# Control_circuit.net
KiCad netlist of a schematic drawn in Altium Designer
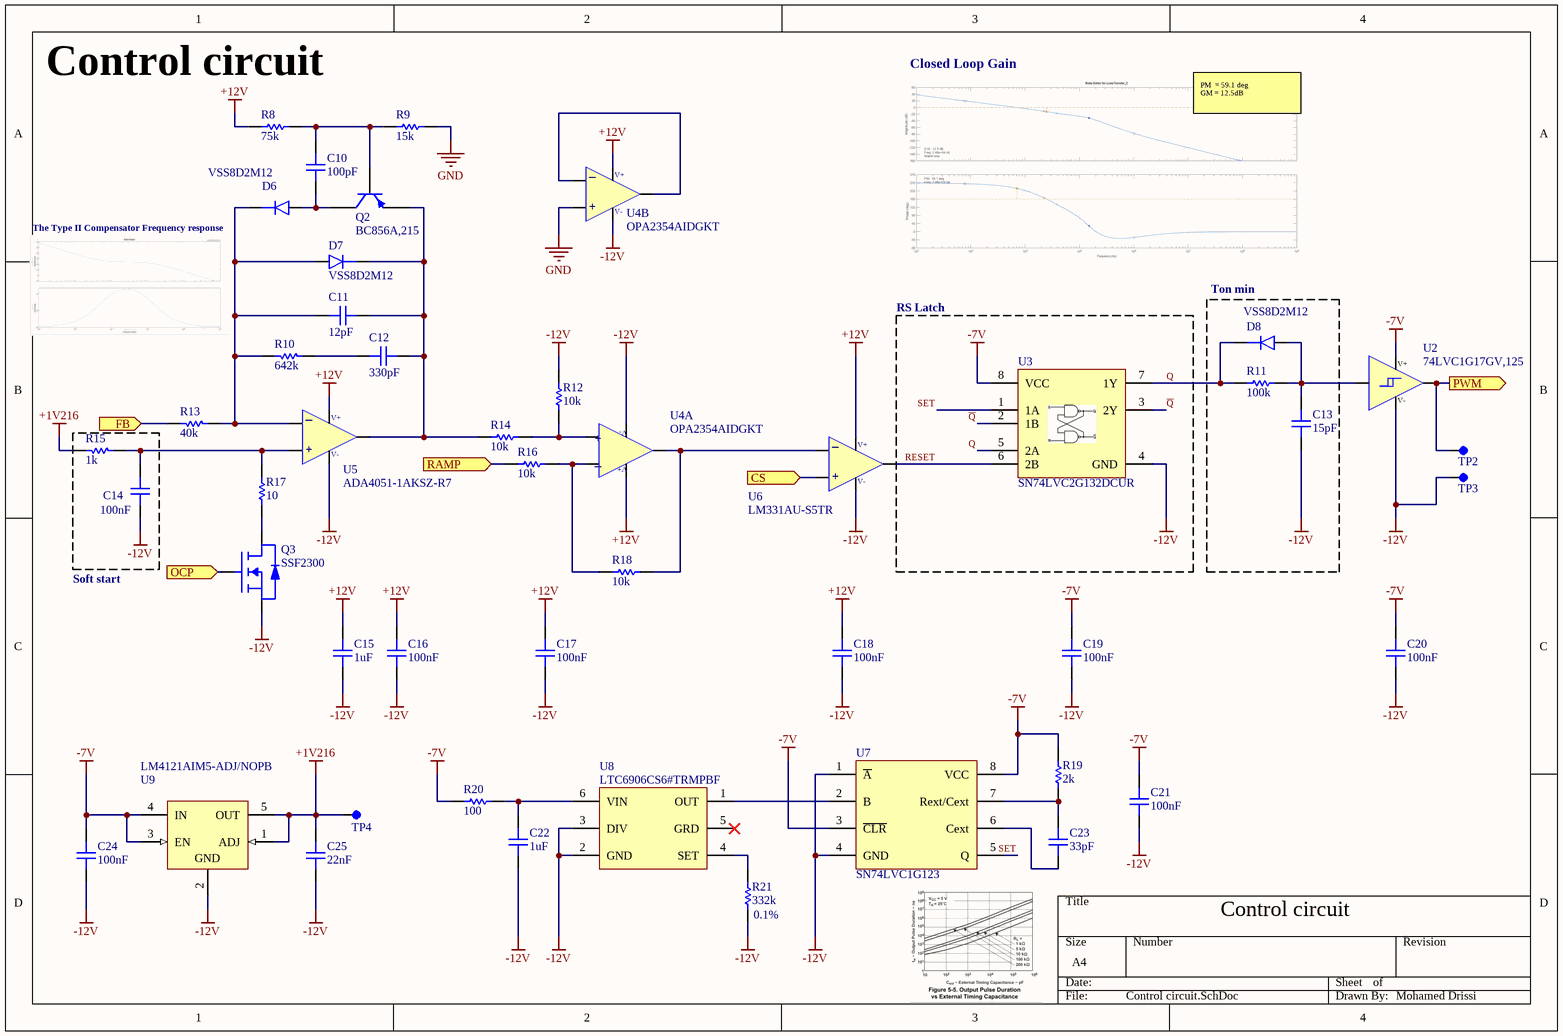
[diagram p0: Control circuit.SchDoc]

(export (version "E")
  (design (tool "Eeschema 10.0.6"))
  (components
    (comp (ref "C10")
      (value "GCM1885C2A101JA16D")
      (footprint "Cap_0603")
      (description "100V 100pF C0G ±5% 0603 Multilayer Ceramic Capacitors MLCC - SMD/SMT ROHS")
      (fields
        (field (name "MANUFACTURER") "Murata")
        (field (name "TOLERANCE") "5%")
        (field (name "CAPACITANCE") "100pF")
      )
      (libsource (lib "Inverting buck boost") (part "Murata GCM1885C2A101JA16D"))
    )
    (comp (ref "C11")
      (value "VJ0603A120KXJCW1BC")
      (footprint "cap_0603")
      (fields
        (field (name "MANUFACTURER") "Vishay")
        (field (name "TOLERANCE") "10%")
        (field (name "CAPACITANCE") "12pF")
      )
      (libsource (lib "Inverting buck boost") (part "Vishay VJ0603A120KXJCW1BC"))
    )
    (comp (ref "C12")
      (value "885012006026")
      (footprint "Cap_0603")
      (description "WCAP-CSGP 0603 (1608Metric) Ceramic Capacitor 0.063Lx0.031W 1.60mmx0.80mm C0G NP0 ±5% 330pF")
      (fields
        (field (name "MANUFACTURER") "Wurth Elektronik")
        (field (name "TOLERANCE") "5%")
        (field (name "CAPACITANCE") "330pF")
      )
      (libsource (lib "Inverting buck boost") (part "Wurth 885012006026"))
    )
    (comp (ref "C13")
      (value "CL10C150JC81PNC")
      (footprint "cap_0603")
      (description "100V 15pF C0G 卤5% 0603 Multilayer Ceramic Capacitors MLCC - SMD/SMT ROHS")
      (fields
        (field (name "MANUFACTURER") "Samsung Electro-Mechanics")
        (field (name "TOLERANCE") "5%")
        (field (name "CAPACITANCE") "15pF")
      )
      (libsource (lib "Inverting buck boost") (part "Samsung CL10C150JC81PNC"))
    )
    (comp (ref "C14")
      (value "GMC10X7R104K100NT")
      (footprint "cap_0603")
      (description "100V 100nF X7R ±10% 0603 Multilayer Ceramic Capacitors MLCC - SMD/SMT ROHS")
      (fields (field (name "MANUFACTURER") "Cal-Chip Electronics") (field (name "CAPACITANCE") "100nF"))
      (libsource (lib "Inverting buck boost") (part "Cal-chip GMC10X7R104K100NT"))
    )
    (comp (ref "C15")
      (value "885382208005")
      (footprint "cap_1206")
      (description "WCAP-CSST 1206 (3216Metric) ceramic capacitor 0.126Lx0.063W 3.20mmx1.60mm X7R ±10% 1muF")
      (fields (field (name "MANUFACTURER") "Wurth Elektronik") (field (name "CAPACITANCE") "1uF"))
      (libsource (lib "Inverting buck boost") (part "Wurth 885382208005"))
    )
    (comp (ref "C16")
      (value "GMC10X7R104K100NT")
      (footprint "cap_0603")
      (description "100V 100nF X7R ±10% 0603 Multilayer Ceramic Capacitors MLCC - SMD/SMT ROHS")
      (fields (field (name "MANUFACTURER") "Cal-Chip Electronics") (field (name "CAPACITANCE") "100nF"))
      (libsource (lib "Inverting buck boost") (part "Cal-chip GMC10X7R104K100NT"))
    )
    (comp (ref "C17")
      (value "GMC10X7R104K100NT")
      (footprint "cap_0603")
      (description "100V 100nF X7R ±10% 0603 Multilayer Ceramic Capacitors MLCC - SMD/SMT ROHS")
      (fields (field (name "MANUFACTURER") "Cal-Chip Electronics") (field (name "CAPACITANCE") "100nF"))
      (libsource (lib "Inverting buck boost") (part "Cal-chip GMC10X7R104K100NT"))
    )
    (comp (ref "C18")
      (value "GMC10X7R104K100NT")
      (footprint "cap_0603")
      (description "100V 100nF X7R ±10% 0603 Multilayer Ceramic Capacitors MLCC - SMD/SMT ROHS")
      (fields (field (name "MANUFACTURER") "Cal-Chip Electronics") (field (name "CAPACITANCE") "100nF"))
      (libsource (lib "Inverting buck boost") (part "Cal-chip GMC10X7R104K100NT"))
    )
    (comp (ref "C19")
      (value "GMC10X7R104K100NT")
      (footprint "cap_0603")
      (description "100V 100nF X7R ±10% 0603 Multilayer Ceramic Capacitors MLCC - SMD/SMT ROHS")
      (fields (field (name "MANUFACTURER") "Cal-Chip Electronics") (field (name "CAPACITANCE") "100nF"))
      (libsource (lib "Inverting buck boost") (part "Cal-chip GMC10X7R104K100NT"))
    )
    (comp (ref "C20")
      (value "GMC10X7R104K100NT")
      (footprint "cap_0603")
      (description "100V 100nF X7R ±10% 0603 Multilayer Ceramic Capacitors MLCC - SMD/SMT ROHS")
      (fields (field (name "MANUFACTURER") "Cal-Chip Electronics") (field (name "CAPACITANCE") "100nF"))
      (libsource (lib "Inverting buck boost") (part "Cal-chip GMC10X7R104K100NT"))
    )
    (comp (ref "C21")
      (value "GMC10X7R104K100NT")
      (footprint "cap_0603")
      (description "100V 100nF X7R ±10% 0603 Multilayer Ceramic Capacitors MLCC - SMD/SMT ROHS")
      (fields (field (name "MANUFACTURER") "Cal-Chip Electronics") (field (name "CAPACITANCE") "100nF"))
      (libsource (lib "Inverting buck boost") (part "Cal-chip GMC10X7R104K100NT"))
    )
    (comp (ref "C22")
      (value "CL10B105KA8NNNC")
      (footprint "cap_0603")
      (description "25V 1uF X7R 卤10% 0603 Multilayer Ceramic Capacitors MLCC - SMD/SMT ROHS")
      (fields
        (field (name "MANUFACTURER") "Samsung Electro-Mechanics")
        (field (name "TOLERANCE") "10%")
        (field (name "CAPACITANCE") "1uF")
      )
      (libsource (lib "Inverting buck boost") (part "Samsung CL10B105KA8NNNC"))
    )
    (comp (ref "C23")
      (value "CL10C330JB8NNNC")
      (footprint "cap_0603")
      (description "Multilayer Ceramic Capacitor, 33 pF, 50 V, ± 5%, C0G (NP0), 0603 [1608 Metric]")
      (fields
        (field (name "MANUFACTURER") "Samsung Electro-Mechanics")
        (field (name "TOLERANCE") "5%")
        (field (name "CAPACITANCE") "33pF")
      )
      (libsource (lib "Inverting buck boost") (part "Samsung CL10C330JB8NNNC"))
    )
    (comp (ref "C24")
      (value "GMC10X7R104K100NT")
      (footprint "cap_0603")
      (description "100V 100nF X7R ±10% 0603 Multilayer Ceramic Capacitors MLCC - SMD/SMT ROHS")
      (fields (field (name "MANUFACTURER") "Cal-Chip Electronics") (field (name "CAPACITANCE") "100nF"))
      (libsource (lib "Inverting buck boost") (part "Cal-chip GMC10X7R104K100NT"))
    )
    (comp (ref "C25")
      (value "C0603C223K4RACTU")
      (footprint "cap_0603")
      (description "Multilayer Ceramic Capacitors MLCC – SMD/SMT; KEMET; C0603C223K4RACTU; 22 nF; 0603; 16 V; 16 V")
      (fields
        (field (name "MANUFACTURER") "Yageo Group")
        (field (name "TOLERANCE") "10%")
        (field (name "CAPACITANCE") "22nF")
      )
      (libsource (lib "Inverting buck boost") (part "Yageo C0603C223K4RACTU"))
    )
    (comp (ref "D6")
      (value "VSS8D2M12")
      (footprint "DO-221AD")
      (description "Rectifier Diode, Schottky, 1 Phase, 1 Element, 2A, 120V V(RRM), Silicon, DO-221AD")
      (fields
        (field (name "MANUFACTURER") "Vishay")
        (field (name "MANUFACTURER PART NUMBER") "VSS8D2M12-M3/H")
      )
      (libsource (lib "Inverting buck boost") (part "Vishay VSS8D2M12-M3/H"))
    )
    (comp (ref "D7")
      (value "VSS8D2M12")
      (footprint "DO-221AD")
      (description "Rectifier Diode, Schottky, 1 Phase, 1 Element, 2A, 120V V(RRM), Silicon, DO-221AD")
      (fields
        (field (name "MANUFACTURER") "Vishay")
        (field (name "MANUFACTURER PART NUMBER") "VSS8D2M12-M3/H")
      )
      (libsource (lib "Inverting buck boost") (part "Vishay VSS8D2M12-M3/H"))
    )
    (comp (ref "D8")
      (value "VSS8D2M12")
      (footprint "DO-221AD")
      (description "Rectifier Diode, Schottky, 1 Phase, 1 Element, 2A, 120V V(RRM), Silicon, DO-221AD")
      (fields
        (field (name "MANUFACTURER") "Vishay")
        (field (name "MANUFACTURER PART NUMBER") "VSS8D2M12-M3/H")
      )
      (libsource (lib "Inverting buck boost") (part "Vishay VSS8D2M12-M3/H"))
    )
    (comp (ref "Q2")
      (value "BC856A,215")
      (footprint "sot23")
      (description "BC856 Series 65 V 100 mA SMT PNP General Purpose Transistor - SOT-23")
      (fields (field (name "MANUFACTURER") "Nexperia"))
      (libsource (lib "Inverting buck boost") (part "NXP BC856A,215"))
    )
    (comp (ref "Q3")
      (value "SSF2300")
      (footprint "SOT-23-3")
      (description "Trans Mosfet N-ch 20V 4.5A 3-PIN SOT-23 T/r")
      (libsource (lib "Inverting buck boost") (part "Semiconductor SSF2300"))
    )
    (comp (ref "R8")
      (value "CRCW060375K0FKEAC")
      (footprint "Res_0603")
      (description "100mW Thick Film Resistors 75V ±100ppm/℃ ±1% 15kΩ 0603 Chip Resistor - Surface Mount ROHS")
      (fields
        (field (name "MANUFACTURER") "Vishay")
        (field (name "TOLERANCE") "1%")
        (field (name "RESISTANCE") "75k")
      )
      (libsource (lib "Inverting buck boost") (part "Vishay CRCW060375K0FKEAC"))
    )
    (comp (ref "R9")
      (value "RC0603FR-0715KL")
      (footprint "Res_0603")
      (description "100mW Thick Film Resistors 75V ±100ppm/℃ ±1% 15kΩ 0603 Chip Resistor - Surface Mount ROHS")
      (fields (field (name "RESISTANCE") "15k"))
      (libsource (lib "Inverting buck boost") (part "Yageo RC0603FR-0715KL"))
    )
    (comp (ref "R10")
      (value "642k")
      (footprint "res_0603")
      (description "Fixed Resistor, Thin Film, 0.1W, 642000ohm, 75V, 0.1% +/-Tol, Surface Mount, 0603")
      (fields
        (field (name "MANUFACTURER") "KOA Speer")
        (field (name "MANUFACTURER PART NUMBER") "RN73H1JTTD6423B50")
      )
      (libsource (lib "Inverting buck boost") (part "TOA RN73H1JTTD6423B50"))
    )
    (comp (ref "R11")
      (value "CRCW0603100KFKEA")
      (footprint "res_0603")
      (description "Res Thick Film 0603 100K Ohm 1% 1/3W ±100ppm/°C Molded SMD SMD Paper T/R")
      (fields
        (field (name "MANUFACTURER") "Vishay")
        (field (name "MANUFACTURER PART NUMBER") "CRCW0603100KFKEAHP")
        (field (name "RESISTANCE") "100k")
      )
      (libsource (lib "Inverting buck boost") (part "Vishay CRCW0603100KFKEAHP"))
    )
    (comp (ref "R12")
      (value "ERA-3AEB103V")
      (footprint "res_0603")
      (description "Res Thin Film 0603 10K Ohm 0.1% 1/10W ±25ppm/°C Molded SMD SMD Punched Carrier T/R")
      (fields
        (field (name "MANUFACTURER") "Panasonic")
        (field (name "TOLERANCE") "0.1%")
        (field (name "RESISTANCE") "10k")
      )
      (libsource (lib "Inverting buck boost") (part "Panasonic ERA-3AEB103V"))
    )
    (comp (ref "R13")
      (value "40k")
      (footprint "Res_0603")
      (description "100mW Thin Film Resistor ±25ppm/℃ ±0.1% 40kΩ 0603 Chip Resistor - Surface Mount ROHS")
      (fields
        (field (name "MANUFACTURER") "Yageo Group")
        (field (name "MANUFACTURER PART NUMBER") "AT0603BRD0740KL")
      )
      (libsource (lib "Inverting buck boost") (part "Yageo AT0603BRD0740KL"))
    )
    (comp (ref "R14")
      (value "ERA-3AEB103V")
      (footprint "res_0603")
      (description "Res Thin Film 0603 10K Ohm 0.1% 1/10W ±25ppm/°C Molded SMD SMD Punched Carrier T/R")
      (fields
        (field (name "MANUFACTURER") "Panasonic")
        (field (name "TOLERANCE") "0.1%")
        (field (name "RESISTANCE") "10k")
      )
      (libsource (lib "Inverting buck boost") (part "Panasonic ERA-3AEB103V"))
    )
    (comp (ref "R15")
      (value "RC0603FR-071KL")
      (footprint "res_0603")
      (description "Res Thick Film 0603 1K Ohm 1% 0.1W(1/10W) ±100ppm/°C Pad SMD T/R / RES SMD 1K OHM 1% 1/10W 0603")
      (fields
        (field (name "MANUFACTURER") "Yageo Group")
        (field (name "TOLERANCE") "1%")
        (field (name "RESISTANCE") "1k")
      )
      (libsource (lib "Inverting buck boost") (part "Yageo RC0603FR-071KL"))
    )
    (comp (ref "R16")
      (value "ERA-3AEB103V")
      (footprint "res_0603")
      (description "Res Thin Film 0603 10K Ohm 0.1% 1/10W ±25ppm/°C Molded SMD SMD Punched Carrier T/R")
      (fields
        (field (name "MANUFACTURER") "Panasonic")
        (field (name "TOLERANCE") "0.1%")
        (field (name "RESISTANCE") "10k")
      )
      (libsource (lib "Inverting buck boost") (part "Panasonic ERA-3AEB103V"))
    )
    (comp (ref "R17")
      (value "RC0603FR-0710RL")
      (footprint "res_0603")
      (description "Res Thick Film 0603 10 Ohm 1% 0.1W(1/10W) ±200ppm/C Pad SMD T/R")
      (fields (field (name "RESISTANCE") "10"))
      (libsource (lib "Inverting buck boost") (part "Yageo RC0603FR-0710RL"))
    )
    (comp (ref "R18")
      (value "ERA-3AEB103V")
      (footprint "res_0603")
      (description "Res Thin Film 0603 10K Ohm 0.1% 1/10W ±25ppm/°C Molded SMD SMD Punched Carrier T/R")
      (fields
        (field (name "MANUFACTURER") "Panasonic")
        (field (name "TOLERANCE") "0.1%")
        (field (name "RESISTANCE") "10k")
      )
      (libsource (lib "Inverting buck boost") (part "Panasonic ERA-3AEB103V"))
    )
    (comp (ref "R19")
      (value "RT0603BRD072KL")
      (footprint "res_0603")
      (description "Res Thin Film 0603 2K Ohm 0.1% 1/10W ±25ppm/°C Molded SMD SMD Paper T/R")
      (fields
        (field (name "MANUFACTURER") "Yageo Group")
        (field (name "TOLERANCE") "0.1%")
        (field (name "RESISITANCE") "2k")
      )
      (libsource (lib "Inverting buck boost") (part "Yageo RT0603BRD072KL"))
    )
    (comp (ref "R20")
      (value "RC0603FR-07100RL")
      (footprint "res_0603")
      (description "Yageo RC0603FR-07100RL 0603 SMD Resistor 100 Ohm thin film chip resistor")
      (fields
        (field (name "MANUFACTURER") "Yageo Group")
        (field (name "TOLERANCE") "1%")
        (field (name "RESISTANCE") "100")
      )
      (libsource (lib "Inverting buck boost") (part "Yageo RC0603FR-07100RL"))
    )
    (comp (ref "R21")
      (value "RT0603BRD07332KL")
      (footprint "res_0603")
      (description "100mW Thin Film Resistor ±25ppm/℃ ±0.1% 332kΩ 0603 Chip Resistor - Surface Mount ROHS")
      (fields
        (field (name "MANUFACTURER") "Yageo Group")
        (field (name "TOLERANCE") "0.1%")
        (field (name "RESISTANCE") "332k")
      )
      (libsource (lib "Inverting buck boost") (part "Yageo RT0603BRD07332KL"))
    )
    (comp (ref "TP2")
      (value "5000")
      (footprint "TH TP")
      (description "Cable Wrap, 1/2 Inch, Polyethylene, Natural, 50 Ft, Spirap Series ¦ TE Connectivity 500002-1")
      (fields (field (name "MANUFACTURER") "Keystone"))
      (libsource (lib "Inverting buck boost") (part "Keystone 5000"))
    )
    (comp (ref "TP3")
      (value "5000")
      (footprint "TH TP")
      (description "Cable Wrap, 1/2 Inch, Polyethylene, Natural, 50 Ft, Spirap Series ¦ TE Connectivity 500002-1")
      (fields (field (name "MANUFACTURER") "Keystone"))
      (libsource (lib "Inverting buck boost") (part "Keystone 5000"))
    )
    (comp (ref "TP4")
      (value "5000")
      (footprint "TH TP")
      (description "Cable Wrap, 1/2 Inch, Polyethylene, Natural, 50 Ft, Spirap Series ¦ TE Connectivity 500002-1")
      (fields (field (name "MANUFACTURER") "Keystone"))
      (libsource (lib "Inverting buck boost") (part "Keystone 5000"))
    )
    (comp (ref "U2")
      (value "74LVC1G17GV,125")
      (footprint "SOT353-1")
      (description "Schmitt Trigger Buffer, Single, 1 Input, 5 Pins, TSOP, 74LVC1G17")
      (fields (field (name "MANUFACTURER") "Nexperia"))
      (libsource (lib "Inverting buck boost") (part "NXP 74LVC1G17GV,125"))
    )
    (comp (ref "U3")
      (value "SN74LVC2G132DCUR")
      (footprint "8-VSSOP")
      (description "2-ch, 2-input, 1.65-V to 5.5-V NAND gates with Schmitt-Trigger inputs 8-VSSOP -40 to 125")
      (fields (field (name "MANUFACTURER") "Texas Instruments"))
      (libsource (lib "Inverting buck boost") (part "TI SN74LVC2G132DCUR"))
    )
    (comp (ref "U4")
      (value "OPA2354AIDGKT")
      (footprint "TSOP, 8-Leads")
      (description "250MHz, Rail-to-Rail I/O, CMOS Dual Operational Amplifier 8-VSSOP -40 to 125")
      (fields
        (field (name "MANUFACTURER") "Texas Instruments")
        (field (name "MANUFACTURER PART NUMBER") "OPA2354AIDGKR")
      )
      (libsource (lib "Inverting buck boost") (part "TI OPA2354AIDGKT"))
    )
    (comp (ref "U5")
      (value "ADA4051-1AKSZ-R7")
      (footprint "5-Lead SOT-23")
      (description "Op Amp Single Micropower Amplifier R-R I/O 5.5V 5-Pin SC-70 T/R")
      (fields (field (name "MANUFACTURER") "Analog Devices"))
      (libsource (lib "Inverting buck boost") (part "Analog Device ADA4051-1AKSZ-R7"))
    )
    (comp (ref "U6")
      (value "LM331AU-S5TR")
      (footprint "5-Lead SOT-23")
      (description "150μA 500ns Open Collector, Rail to Rail 20mA 1 2.5V ±18V, 36V 6mV@ 5V 4nA@ 5V SOT-23-5 , 2.9mm")
      (fields (field (name "MANUFACTURER") "3Peak"))
      (libsource (lib "Inverting buck boost") (part "3Peak LM331AU-S5TR"))
    )
    (comp (ref "U7")
      (value "SN74LVC1G123")
      (footprint "8-VSSOP")
      (description "Single retriggerable monostable multivibrator with Schmitt-trigger inputs 8-VSSOP -40 to 125")
      (fields
        (field (name "MANUFACTURER") "Texas Instruments")
        (field (name "MANUFACTURER PART NUMBER") "SN74LVC1G123DCUR")
      )
      (libsource (lib "Inverting buck boost") (part "TI SN74LVC1G123DCUR"))
    )
    (comp (ref "U8")
      (value "LTC6906CS6#TRMPBF")
      (footprint "sot23-6")
      (description "Silicon Oscillator 0.01MHz to 1MHz CMOS Automotive 6-Pin TSOT-23 Tape and Reel")
      (fields (field (name "MANUFACTURER") "Analog Devices"))
      (libsource (lib "Inverting buck boost") (part "LT LTC6906CS6#TRMPBF"))
    )
    (comp (ref "U9")
      (value "LM4121AIM5-ADJ/NOPB")
      (footprint "5-Lead SOT-23")
      (description "V-Ref Adjustable 1.214V to 1.218V 5mA 5-Pin SOT-23 T/R")
      (fields (field (name "MANUFACTURER") "Texas Instruments") (field (name "TOLERANCE") "0.2%"))
      (libsource (lib "Inverting buck boost") (part "TI LM4121AIM5-ADJ/NOPB"))
    )
  )
  (nets
    (net (code "1") (name "+1V216") (class "Default")
      (node (ref "C25") (pin "2") (pinfunction "2_2") (pintype "passive"))
      (node (ref "R15") (pin "2") (pinfunction "2_2") (pintype "passive"))
      (node (ref "TP4") (pin "1") (pinfunction "1_1") (pintype "passive"))
      (node (ref "U9") (pin "1") (pinfunction "ADJ_1") (pintype "input"))
      (node (ref "U9") (pin "5") (pinfunction "OUT_5") (pintype "power_in"))
    )
    (net (code "2") (name "+12V") (class "Default")
      (node (ref "C15") (pin "1") (pinfunction "1_1") (pintype "passive"))
      (node (ref "C16") (pin "2") (pinfunction "2_2") (pintype "passive"))
      (node (ref "C17") (pin "2") (pinfunction "2_2") (pintype "passive"))
      (node (ref "C18") (pin "2") (pinfunction "2_2") (pintype "passive"))
      (node (ref "R8") (pin "1") (pinfunction "1_1") (pintype "passive"))
      (node (ref "U4") (pin "8") (pinfunction "V+_8") (pintype "passive"))
      (node (ref "U5") (pin "5") (pinfunction "V+_5") (pintype "passive"))
      (node (ref "U6") (pin "5") (pinfunction "V+_5") (pintype "passive"))
    )
    (net (code "3") (name "-7V") (class "Default")
      (node (ref "C19") (pin "2") (pinfunction "2_2") (pintype "passive"))
      (node (ref "C20") (pin "2") (pinfunction "2_2") (pintype "passive"))
      (node (ref "C21") (pin "2") (pinfunction "2_2") (pintype "passive"))
      (node (ref "C24") (pin "2") (pinfunction "2_2") (pintype "passive"))
      (node (ref "R19") (pin "2") (pinfunction "2_2") (pintype "passive"))
      (node (ref "R20") (pin "1") (pinfunction "1_1") (pintype "passive"))
      (node (ref "U2") (pin "5") (pinfunction "V+_5") (pintype "passive"))
      (node (ref "U3") (pin "8") (pinfunction "VCC_8") (pintype "power_in"))
      (node (ref "U7") (pin "3") (pinfunction "~{CLR}_3") (pintype "passive"))
      (node (ref "U7") (pin "8") (pinfunction "VCC_8") (pintype "power_in"))
      (node (ref "U9") (pin "3") (pinfunction "EN_3") (pintype "input"))
      (node (ref "U9") (pin "4") (pinfunction "IN_4") (pintype "power_in"))
    )
    (net (code "4") (name "-12V") (class "Default")
      (node (ref "C13") (pin "1") (pinfunction "1_1") (pintype "passive"))
      (node (ref "C14") (pin "1") (pinfunction "1_1") (pintype "passive"))
      (node (ref "C15") (pin "2") (pinfunction "2_2") (pintype "passive"))
      (node (ref "C16") (pin "1") (pinfunction "1_1") (pintype "passive"))
      (node (ref "C17") (pin "1") (pinfunction "1_1") (pintype "passive"))
      (node (ref "C18") (pin "1") (pinfunction "1_1") (pintype "passive"))
      (node (ref "C19") (pin "1") (pinfunction "1_1") (pintype "passive"))
      (node (ref "C20") (pin "1") (pinfunction "1_1") (pintype "passive"))
      (node (ref "C21") (pin "1") (pinfunction "1_1") (pintype "passive"))
      (node (ref "C22") (pin "1") (pinfunction "1_1") (pintype "passive"))
      (node (ref "C24") (pin "1") (pinfunction "1_1") (pintype "passive"))
      (node (ref "C25") (pin "1") (pinfunction "1_1") (pintype "passive"))
      (node (ref "Q3") (pin "1") (pinfunction "S_1") (pintype "passive"))
      (node (ref "R12") (pin "2") (pinfunction "2_2") (pintype "passive"))
      (node (ref "R21") (pin "1") (pinfunction "1_1") (pintype "passive"))
      (node (ref "TP3") (pin "1") (pinfunction "1_1") (pintype "passive"))
      (node (ref "U2") (pin "3") (pinfunction "V-_3") (pintype "passive"))
      (node (ref "U3") (pin "4") (pinfunction "GND_4") (pintype "power_in"))
      (node (ref "U4") (pin "4") (pinfunction "V-_4") (pintype "passive"))
      (node (ref "U5") (pin "2") (pinfunction "V-_2") (pintype "passive"))
      (node (ref "U6") (pin "2") (pinfunction "V-_2") (pintype "passive"))
      (node (ref "U7") (pin "1") (pinfunction "~{A}_1") (pintype "passive"))
      (node (ref "U7") (pin "4") (pinfunction "GND_4") (pintype "power_in"))
      (node (ref "U8") (pin "2") (pinfunction "GND_2") (pintype "passive"))
      (node (ref "U8") (pin "3") (pinfunction "DIV_3") (pintype "passive"))
      (node (ref "U9") (pin "2") (pinfunction "GND_2") (pintype "power_in"))
    )
    (net (code "5") (name "/CS") (class "Default")
      (node (ref "U6") (pin "1") (pinfunction "IN-_1") (pintype "passive"))
    )
    (net (code "6") (name "/FB") (class "Default")
      (node (ref "R13") (pin "2") (pinfunction "2_2") (pintype "passive"))
    )
    (net (code "7") (name "/OCP") (class "Default")
      (node (ref "Q3") (pin "2") (pinfunction "G_2") (pintype "passive"))
    )
    (net (code "8") (name "/PWM") (class "Default")
      (node (ref "TP2") (pin "1") (pinfunction "1_1") (pintype "passive"))
      (node (ref "U2") (pin "4") (pinfunction "Y_4") (pintype "passive"))
    )
    (net (code "9") (name "/Q") (class "Default")
      (node (ref "D8") (pin "C") (pinfunction "C_C") (pintype "passive"))
      (node (ref "R11") (pin "1") (pinfunction "1_1") (pintype "passive"))
      (node (ref "U3") (pin "5") (pinfunction "2A_5") (pintype "open_collector"))
      (node (ref "U3") (pin "7") (pinfunction "1Y_7") (pintype "passive"))
    )
    (net (code "10") (name "/RAMP") (class "Default")
      (node (ref "R16") (pin "1") (pinfunction "1_1") (pintype "passive"))
    )
    (net (code "11") (name "/RESET") (class "Default")
      (node (ref "U3") (pin "6") (pinfunction "2B_6") (pintype "open_collector"))
      (node (ref "U6") (pin "4") (pinfunction "OUT_4") (pintype "passive"))
    )
    (net (code "12") (name "/SET") (class "Default")
      (node (ref "U3") (pin "1") (pinfunction "1A_1") (pintype "open_collector"))
      (node (ref "U7") (pin "5") (pinfunction "Q_5") (pintype "passive"))
    )
    (net (code "13") (name "/~{Q}") (class "Default")
      (node (ref "U3") (pin "2") (pinfunction "1B_2") (pintype "open_collector"))
      (node (ref "U3") (pin "3") (pinfunction "2Y_3") (pintype "passive"))
    )
    (net (code "14") (name "GND") (class "Default")
      (node (ref "R9") (pin "2") (pinfunction "2_2") (pintype "passive"))
      (node (ref "U4") (pin "5") (pinfunction "IN-_5") (pintype "passive"))
    )
    (net (code "15") (name "Net-(C12-Pad2)") (class "Default")
      (node (ref "C12") (pin "2") (pinfunction "2_2") (pintype "passive"))
      (node (ref "R10") (pin "1") (pinfunction "1_1") (pintype "passive"))
    )
    (net (code "16") (name "Net-(Q2-B)") (class "Default")
      (node (ref "C10") (pin "2") (pinfunction "2_2") (pintype "passive"))
      (node (ref "Q2") (pin "1") (pinfunction "B_1") (pintype "passive"))
      (node (ref "R8") (pin "2") (pinfunction "2_2") (pintype "passive"))
      (node (ref "R9") (pin "1") (pinfunction "1_1") (pintype "passive"))
    )
    (net (code "17") (name "Net-(Q2-C)") (class "Default")
      (node (ref "C10") (pin "1") (pinfunction "1_1") (pintype "passive"))
      (node (ref "D6") (pin "A") (pinfunction "A_A") (pintype "passive"))
      (node (ref "Q2") (pin "3") (pinfunction "C_3") (pintype "passive"))
    )
    (net (code "18") (name "Net-(Q2-E)") (class "Default")
      (node (ref "C11") (pin "1") (pinfunction "1_1") (pintype "passive"))
      (node (ref "C12") (pin "1") (pinfunction "1_1") (pintype "passive"))
      (node (ref "D7") (pin "C") (pinfunction "C_C") (pintype "passive"))
      (node (ref "Q2") (pin "2") (pinfunction "E_2") (pintype "passive"))
      (node (ref "R14") (pin "1") (pinfunction "1_1") (pintype "passive"))
      (node (ref "U5") (pin "4") (pinfunction "OUT_4") (pintype "passive"))
    )
    (net (code "19") (name "Net-(Q3-D)") (class "Default")
      (node (ref "Q3") (pin "3") (pinfunction "D_3") (pintype "passive"))
      (node (ref "R17") (pin "1") (pinfunction "1_1") (pintype "passive"))
    )
    (net (code "20") (name "Net-(U2-A)") (class "Default")
      (node (ref "C13") (pin "2") (pinfunction "2_2") (pintype "passive"))
      (node (ref "D8") (pin "A") (pinfunction "A_A") (pintype "passive"))
      (node (ref "R11") (pin "2") (pinfunction "2_2") (pintype "passive"))
      (node (ref "U2") (pin "2") (pinfunction "A_2") (pintype "passive"))
    )
    (net (code "21") (name "Net-(U4A-IN+)") (class "Default")
      (node (ref "R16") (pin "2") (pinfunction "2_2") (pintype "passive"))
      (node (ref "R18") (pin "1") (pinfunction "1_1") (pintype "passive"))
      (node (ref "U4") (pin "2") (pinfunction "IN+_2") (pintype "passive"))
    )
    (net (code "22") (name "Net-(U4A-IN-)") (class "Default")
      (node (ref "R12") (pin "1") (pinfunction "1_1") (pintype "passive"))
      (node (ref "R14") (pin "2") (pinfunction "2_2") (pintype "passive"))
      (node (ref "U4") (pin "3") (pinfunction "IN-_3") (pintype "passive"))
    )
    (net (code "23") (name "Net-(U4A-OUT)") (class "Default")
      (node (ref "R18") (pin "2") (pinfunction "2_2") (pintype "passive"))
      (node (ref "U4") (pin "1") (pinfunction "OUT_1") (pintype "passive"))
      (node (ref "U6") (pin "3") (pinfunction "IN+_3") (pintype "passive"))
    )
    (net (code "24") (name "Net-(U4B-IN+)") (class "Default")
      (node (ref "U4") (pin "6") (pinfunction "IN+_6") (pintype "passive"))
      (node (ref "U4") (pin "7") (pinfunction "OUT_7") (pintype "passive"))
    )
    (net (code "25") (name "Net-(U5-IN+)") (class "Default")
      (node (ref "C11") (pin "2") (pinfunction "2_2") (pintype "passive"))
      (node (ref "D6") (pin "C") (pinfunction "C_C") (pintype "passive"))
      (node (ref "D7") (pin "A") (pinfunction "A_A") (pintype "passive"))
      (node (ref "R10") (pin "2") (pinfunction "2_2") (pintype "passive"))
      (node (ref "R13") (pin "1") (pinfunction "1_1") (pintype "passive"))
      (node (ref "U5") (pin "3") (pinfunction "IN+_3") (pintype "passive"))
    )
    (net (code "26") (name "Net-(U5-IN-)") (class "Default")
      (node (ref "C14") (pin "2") (pinfunction "2_2") (pintype "passive"))
      (node (ref "R15") (pin "1") (pinfunction "1_1") (pintype "passive"))
      (node (ref "R17") (pin "2") (pinfunction "2_2") (pintype "passive"))
      (node (ref "U5") (pin "1") (pinfunction "IN-_1") (pintype "passive"))
    )
    (net (code "27") (name "Net-(U7-B)") (class "Default")
      (node (ref "U7") (pin "2") (pinfunction "B_2") (pintype "passive"))
      (node (ref "U8") (pin "1") (pinfunction "OUT_1") (pintype "passive"))
    )
    (net (code "28") (name "Net-(U7-Cext)") (class "Default")
      (node (ref "C23") (pin "1") (pinfunction "1_1") (pintype "passive"))
      (node (ref "U7") (pin "6") (pinfunction "Cext_6") (pintype "passive"))
    )
    (net (code "29") (name "Net-(U7-Rext{slash}Cext)") (class "Default")
      (node (ref "C23") (pin "2") (pinfunction "2_2") (pintype "passive"))
      (node (ref "R19") (pin "1") (pinfunction "1_1") (pintype "passive"))
      (node (ref "U7") (pin "7") (pinfunction "Rext/Cext_7") (pintype "passive"))
    )
    (net (code "30") (name "Net-(U8-SET)") (class "Default")
      (node (ref "R21") (pin "2") (pinfunction "2_2") (pintype "passive"))
      (node (ref "U8") (pin "4") (pinfunction "SET_4") (pintype "passive"))
    )
    (net (code "31") (name "Net-(U8-VIN)") (class "Default")
      (node (ref "C22") (pin "2") (pinfunction "2_2") (pintype "passive"))
      (node (ref "R20") (pin "2") (pinfunction "2_2") (pintype "passive"))
      (node (ref "U8") (pin "6") (pinfunction "VIN_6") (pintype "passive"))
    )
    (net (code "32") (name "unconnected-(U8-GRD-Pad5)") (class "Default")
      (node (ref "U8") (pin "5") (pinfunction "GRD_5") (pintype "passive+no_connect"))
    )
  )
)
